# MOTOR.net
KiCad netlist of a schematic drawn in Altium Designer
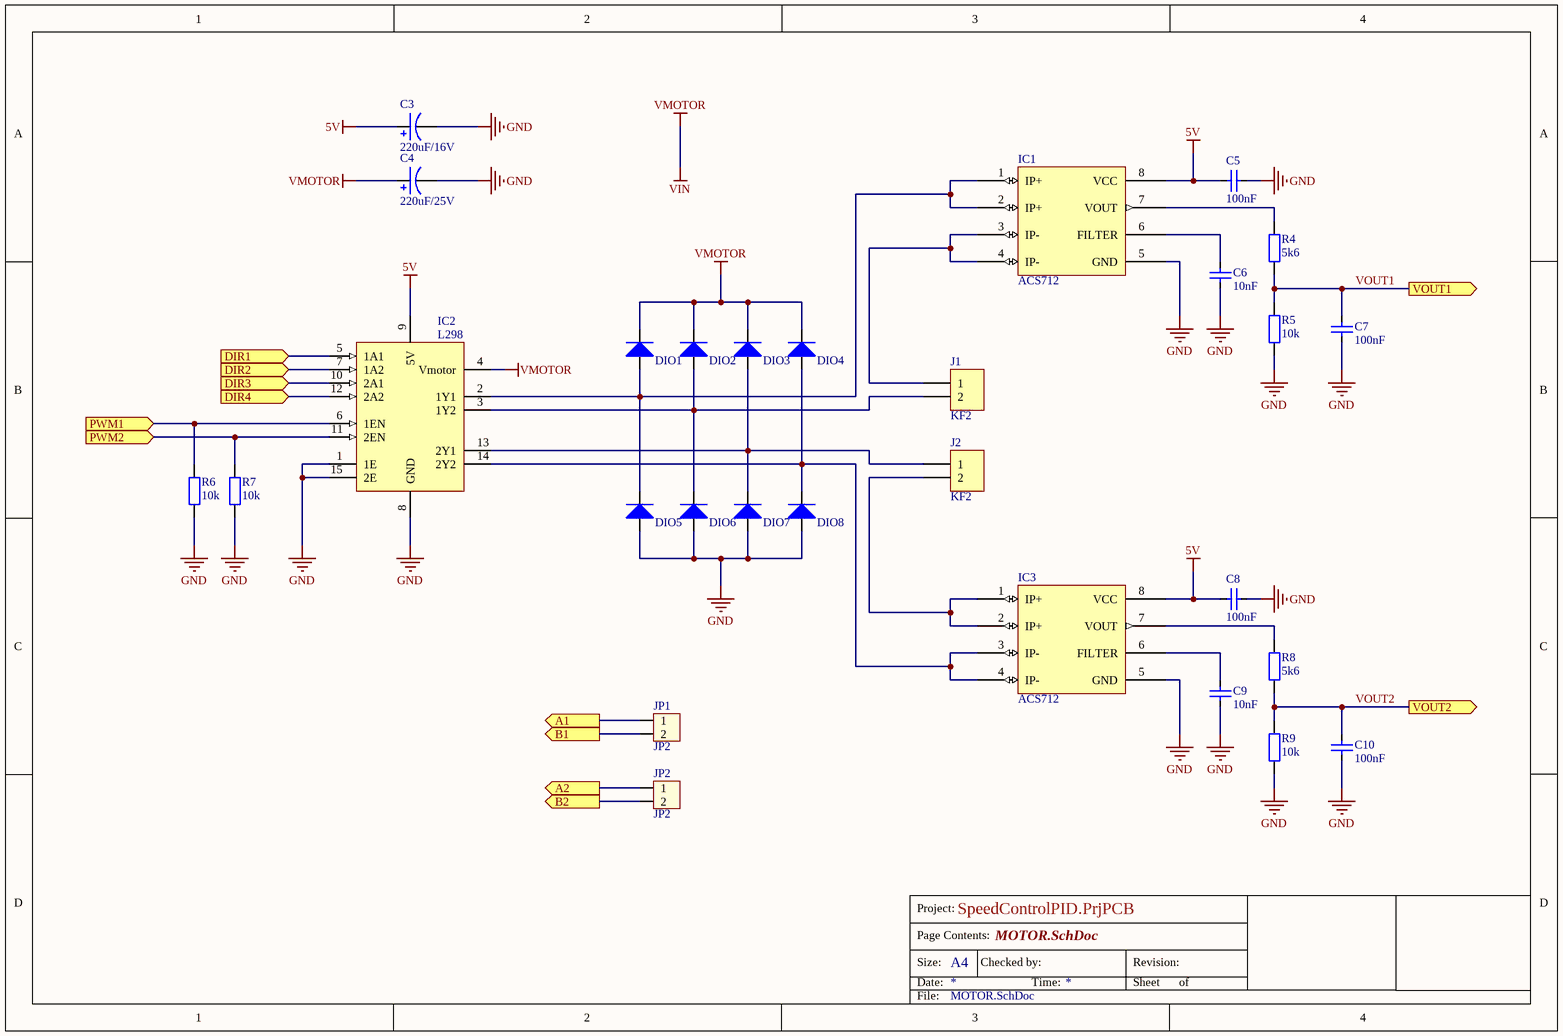
[diagram p0: MOTOR.SchDoc]

(export (version "E")
  (design (tool "Eeschema 10.0.6"))
  (components
    (comp (ref "C3")
      (value "220uF/16V")
      (footprint "C8mm")
      (description "Polarized Capacitor (Axial)")
      (fields (field (name "PUBLISHER") "Altium Limited"))
      (libsource (lib "My Library") (part "Cap Pol"))
    )
    (comp (ref "C4")
      (value "220uF/25V")
      (footprint "C8mm")
      (description "Polarized Capacitor (Axial)")
      (fields (field (name "PUBLISHER") "Altium Limited"))
      (libsource (lib "My Library") (part "Cap Pol"))
    )
    (comp (ref "C5")
      (value "100nF")
      (footprint "CAP_0805")
      (description "Capacitor")
      (fields (field (name "PUBLISHER") "Altium Limited"))
      (libsource (lib "My Library") (part "CapSMD"))
    )
    (comp (ref "C6")
      (value "10nF")
      (footprint "CAP_0805")
      (description "Capacitor")
      (fields (field (name "PUBLISHER") "Altium Limited"))
      (libsource (lib "My Library") (part "CapSMD"))
    )
    (comp (ref "C7")
      (value "100nF")
      (footprint "CAP_0805")
      (description "Capacitor")
      (fields (field (name "PUBLISHER") "Altium Limited"))
      (libsource (lib "My Library") (part "CapSMD"))
    )
    (comp (ref "C8")
      (value "100nF")
      (footprint "CAP_0805")
      (description "Capacitor")
      (fields (field (name "PUBLISHER") "Altium Limited"))
      (libsource (lib "My Library") (part "CapSMD"))
    )
    (comp (ref "C9")
      (value "10nF")
      (footprint "CAP_0805")
      (description "Capacitor")
      (fields (field (name "PUBLISHER") "Altium Limited"))
      (libsource (lib "My Library") (part "CapSMD"))
    )
    (comp (ref "C10")
      (value "100nF")
      (footprint "CAP_0805")
      (description "Capacitor")
      (fields (field (name "PUBLISHER") "Altium Limited"))
      (libsource (lib "My Library") (part "CapSMD"))
    )
    (comp (ref "DIO1")
      (value "Diode SMD")
      (footprint "DIO-214AC(SMA)")
      (description "Default Diode")
      (fields (field (name "PUBLISHER") "Altium Limited"))
      (libsource (lib "My Library") (part "Diode SMD"))
    )
    (comp (ref "DIO2")
      (value "Diode SMD")
      (footprint "DIO-214AC(SMA)")
      (description "Default Diode")
      (fields (field (name "PUBLISHER") "Altium Limited"))
      (libsource (lib "My Library") (part "Diode SMD"))
    )
    (comp (ref "DIO3")
      (value "Diode SMD")
      (footprint "DIO-214AC(SMA)")
      (description "Default Diode")
      (fields (field (name "PUBLISHER") "Altium Limited"))
      (libsource (lib "My Library") (part "Diode SMD"))
    )
    (comp (ref "DIO4")
      (value "Diode SMD")
      (footprint "DIO-214AC(SMA)")
      (description "Default Diode")
      (fields (field (name "PUBLISHER") "Altium Limited"))
      (libsource (lib "My Library") (part "Diode SMD"))
    )
    (comp (ref "DIO5")
      (value "Diode SMD")
      (footprint "DIO-214AC(SMA)")
      (description "Default Diode")
      (fields (field (name "PUBLISHER") "Altium Limited"))
      (libsource (lib "My Library") (part "Diode SMD"))
    )
    (comp (ref "DIO6")
      (value "Diode SMD")
      (footprint "DIO-214AC(SMA)")
      (description "Default Diode")
      (fields (field (name "PUBLISHER") "Altium Limited"))
      (libsource (lib "My Library") (part "Diode SMD"))
    )
    (comp (ref "DIO7")
      (value "Diode SMD")
      (footprint "DIO-214AC(SMA)")
      (description "Default Diode")
      (fields (field (name "PUBLISHER") "Altium Limited"))
      (libsource (lib "My Library") (part "Diode SMD"))
    )
    (comp (ref "DIO8")
      (value "Diode SMD")
      (footprint "DIO-214AC(SMA)")
      (description "Default Diode")
      (fields (field (name "PUBLISHER") "Altium Limited"))
      (libsource (lib "My Library") (part "Diode SMD"))
    )
    (comp (ref "IC1") (value "ACS712") (footprint "SOIC-8") (libsource (lib "My Library") (part "ACS712")))
    (comp (ref "IC2")
      (value "L298")
      (footprint "DIP15SL2")
      (description "Dual Full-H Driver")
      (fields (field (name "PUBLISHER") "Altium Limited"))
      (libsource (lib "My Library") (part "L298"))
    )
    (comp (ref "IC3") (value "ACS712") (footprint "SOIC-8") (libsource (lib "My Library") (part "ACS712")))
    (comp (ref "J1")
      (value "KF2")
      (footprint "KF2-5.08")
      (fields
        (field (name "MANUFACTURER") "Würth Elektronik eiSos GmbH")
        (field (name "PARTNO") "691103110002")
        (field (name "CREATED BY") "Karrer Zheng")
      )
      (libsource (lib "My Library") (part "KF2"))
    )
    (comp (ref "J2")
      (value "KF2")
      (footprint "KF2-5.08")
      (fields
        (field (name "MANUFACTURER") "Würth Elektronik eiSos GmbH")
        (field (name "PARTNO") "691103110002")
        (field (name "CREATED BY") "Karrer Zheng")
      )
      (libsource (lib "My Library") (part "KF2"))
    )
    (comp (ref "JP1")
      (value "JP2")
      (footprint "CON2")
      (description "Connector 2")
      (libsource (lib "My Library") (part "Con2"))
    )
    (comp (ref "JP2")
      (value "JP2")
      (footprint "CON2")
      (description "Connector 2")
      (libsource (lib "My Library") (part "Con2"))
    )
    (comp (ref "R4")
      (value "5k6")
      (footprint "RES-SMD-0805")
      (description "Resistor SMD")
      (fields
        (field (name "MANUFACTURER") "Generic Components")
        (field (name "PUBLISHER") "Altium Hobart Technology Centre")
      )
      (libsource (lib "My Library") (part "Resistor - SMD"))
    )
    (comp (ref "R5")
      (value "10k")
      (footprint "RES-SMD-0805")
      (description "Resistor SMD")
      (fields
        (field (name "MANUFACTURER") "Generic Components")
        (field (name "PUBLISHER") "Altium Hobart Technology Centre")
      )
      (libsource (lib "My Library") (part "Resistor - SMD"))
    )
    (comp (ref "R6")
      (value "10k")
      (footprint "RES-SMD-0805")
      (description "Resistor SMD")
      (fields
        (field (name "MANUFACTURER") "Generic Components")
        (field (name "PUBLISHER") "Altium Hobart Technology Centre")
      )
      (libsource (lib "My Library") (part "Resistor - SMD"))
    )
    (comp (ref "R7")
      (value "10k")
      (footprint "RES-SMD-0805")
      (description "Resistor SMD")
      (fields
        (field (name "MANUFACTURER") "Generic Components")
        (field (name "PUBLISHER") "Altium Hobart Technology Centre")
      )
      (libsource (lib "My Library") (part "Resistor - SMD"))
    )
    (comp (ref "R8")
      (value "5k6")
      (footprint "RES-SMD-0805")
      (description "Resistor SMD")
      (fields
        (field (name "MANUFACTURER") "Generic Components")
        (field (name "PUBLISHER") "Altium Hobart Technology Centre")
      )
      (libsource (lib "My Library") (part "Resistor - SMD"))
    )
    (comp (ref "R9")
      (value "10k")
      (footprint "RES-SMD-0805")
      (description "Resistor SMD")
      (fields
        (field (name "MANUFACTURER") "Generic Components")
        (field (name "PUBLISHER") "Altium Hobart Technology Centre")
      )
      (libsource (lib "My Library") (part "Resistor - SMD"))
    )
  )
  (nets
    (net (code "1") (name "/A1") (class "Default")
      (node (ref "JP1") (pin "1") (pinfunction "1_1") (pintype "passive"))
    )
    (net (code "2") (name "/A2") (class "Default")
      (node (ref "JP2") (pin "1") (pinfunction "1_1") (pintype "passive"))
    )
    (net (code "3") (name "/B1") (class "Default")
      (node (ref "JP1") (pin "2") (pinfunction "2_2") (pintype "passive"))
    )
    (net (code "4") (name "/B2") (class "Default")
      (node (ref "JP2") (pin "2") (pinfunction "2_2") (pintype "passive"))
    )
    (net (code "5") (name "/DIR1") (class "Default")
      (node (ref "IC2") (pin "5") (pinfunction "1A1_5") (pintype "input"))
    )
    (net (code "6") (name "/DIR2") (class "Default")
      (node (ref "IC2") (pin "7") (pinfunction "1A2_7") (pintype "input"))
    )
    (net (code "7") (name "/DIR3") (class "Default")
      (node (ref "IC2") (pin "10") (pinfunction "2A1_10") (pintype "input"))
    )
    (net (code "8") (name "/DIR4") (class "Default")
      (node (ref "IC2") (pin "12") (pinfunction "2A2_12") (pintype "input"))
    )
    (net (code "9") (name "/PWM1") (class "Default")
      (node (ref "IC2") (pin "6") (pinfunction "1EN_6") (pintype "input"))
      (node (ref "R6") (pin "1") (pinfunction "1_1") (pintype "passive"))
    )
    (net (code "10") (name "/PWM2") (class "Default")
      (node (ref "IC2") (pin "11") (pinfunction "2EN_11") (pintype "input"))
      (node (ref "R7") (pin "1") (pinfunction "1_1") (pintype "passive"))
    )
    (net (code "11") (name "/VOUT1") (class "Default")
      (node (ref "C7") (pin "2") (pinfunction "2_2") (pintype "passive"))
      (node (ref "R4") (pin "2") (pinfunction "2_2") (pintype "passive"))
      (node (ref "R5") (pin "1") (pinfunction "1_1") (pintype "passive"))
    )
    (net (code "12") (name "/VOUT2") (class "Default")
      (node (ref "C10") (pin "2") (pinfunction "2_2") (pintype "passive"))
      (node (ref "R8") (pin "2") (pinfunction "2_2") (pintype "passive"))
      (node (ref "R9") (pin "1") (pinfunction "1_1") (pintype "passive"))
    )
    (net (code "13") (name "5V") (class "Default")
      (node (ref "C3") (pin "1") (pinfunction "1_1") (pintype "passive"))
      (node (ref "C5") (pin "2") (pinfunction "2_2") (pintype "passive"))
      (node (ref "C8") (pin "2") (pinfunction "2_2") (pintype "passive"))
      (node (ref "IC1") (pin "8") (pinfunction "VCC_8") (pintype "passive"))
      (node (ref "IC2") (pin "9") (pinfunction "5V_9") (pintype "power_in"))
      (node (ref "IC3") (pin "8") (pinfunction "VCC_8") (pintype "passive"))
    )
    (net (code "14") (name "GND") (class "Default")
      (node (ref "C10") (pin "1") (pinfunction "1_1") (pintype "passive"))
      (node (ref "C3") (pin "2") (pinfunction "2_2") (pintype "passive"))
      (node (ref "C4") (pin "2") (pinfunction "2_2") (pintype "passive"))
      (node (ref "C5") (pin "1") (pinfunction "1_1") (pintype "passive"))
      (node (ref "C6") (pin "1") (pinfunction "1_1") (pintype "passive"))
      (node (ref "C7") (pin "1") (pinfunction "1_1") (pintype "passive"))
      (node (ref "C8") (pin "1") (pinfunction "1_1") (pintype "passive"))
      (node (ref "C9") (pin "1") (pinfunction "1_1") (pintype "passive"))
      (node (ref "DIO5") (pin "1") (pinfunction "A_1") (pintype "passive"))
      (node (ref "DIO6") (pin "1") (pinfunction "A_1") (pintype "passive"))
      (node (ref "DIO7") (pin "1") (pinfunction "A_1") (pintype "passive"))
      (node (ref "DIO8") (pin "1") (pinfunction "A_1") (pintype "passive"))
      (node (ref "IC1") (pin "5") (pinfunction "GND_5") (pintype "passive"))
      (node (ref "IC2") (pin "1") (pinfunction "1E_1") (pintype "passive"))
      (node (ref "IC2") (pin "15") (pinfunction "2E_15") (pintype "passive"))
      (node (ref "IC2") (pin "8") (pinfunction "GND_8") (pintype "power_in"))
      (node (ref "IC3") (pin "5") (pinfunction "GND_5") (pintype "passive"))
      (node (ref "R5") (pin "2") (pinfunction "2_2") (pintype "passive"))
      (node (ref "R6") (pin "2") (pinfunction "2_2") (pintype "passive"))
      (node (ref "R7") (pin "2") (pinfunction "2_2") (pintype "passive"))
      (node (ref "R9") (pin "2") (pinfunction "2_2") (pintype "passive"))
    )
    (net (code "15") (name "Net-(DIO1-A)") (class "Default")
      (node (ref "DIO1") (pin "1") (pinfunction "A_1") (pintype "passive"))
      (node (ref "DIO5") (pin "2") (pinfunction "K_2") (pintype "passive"))
      (node (ref "IC1") (pin "1") (pinfunction "IP+_1") (pintype "bidirectional"))
      (node (ref "IC1") (pin "2") (pinfunction "IP+_2") (pintype "bidirectional"))
      (node (ref "IC2") (pin "2") (pinfunction "1Y1_2") (pintype "tri_state"))
    )
    (net (code "16") (name "Net-(DIO2-A)") (class "Default")
      (node (ref "DIO2") (pin "1") (pinfunction "A_1") (pintype "passive"))
      (node (ref "DIO6") (pin "2") (pinfunction "K_2") (pintype "passive"))
      (node (ref "IC2") (pin "3") (pinfunction "1Y2_3") (pintype "tri_state"))
      (node (ref "J1") (pin "2") (pinfunction "2_2") (pintype "passive"))
    )
    (net (code "17") (name "Net-(DIO3-A)") (class "Default")
      (node (ref "DIO3") (pin "1") (pinfunction "A_1") (pintype "passive"))
      (node (ref "DIO7") (pin "2") (pinfunction "K_2") (pintype "passive"))
      (node (ref "IC2") (pin "13") (pinfunction "2Y1_13") (pintype "tri_state"))
      (node (ref "J2") (pin "1") (pinfunction "1_1") (pintype "passive"))
    )
    (net (code "18") (name "Net-(DIO4-A)") (class "Default")
      (node (ref "DIO4") (pin "1") (pinfunction "A_1") (pintype "passive"))
      (node (ref "DIO8") (pin "2") (pinfunction "K_2") (pintype "passive"))
      (node (ref "IC2") (pin "14") (pinfunction "2Y2_14") (pintype "tri_state"))
      (node (ref "IC3") (pin "3") (pinfunction "IP-_3") (pintype "bidirectional"))
      (node (ref "IC3") (pin "4") (pinfunction "IP-_4") (pintype "bidirectional"))
    )
    (net (code "19") (name "Net-(IC1-FILTER)") (class "Default")
      (node (ref "C6") (pin "2") (pinfunction "2_2") (pintype "passive"))
      (node (ref "IC1") (pin "6") (pinfunction "FILTER_6") (pintype "passive"))
    )
    (net (code "20") (name "Net-(IC1-IP--Pad3)") (class "Default")
      (node (ref "IC1") (pin "3") (pinfunction "IP-_3") (pintype "bidirectional"))
      (node (ref "IC1") (pin "4") (pinfunction "IP-_4") (pintype "bidirectional"))
      (node (ref "J1") (pin "1") (pinfunction "1_1") (pintype "passive"))
    )
    (net (code "21") (name "Net-(IC1-VOUT)") (class "Default")
      (node (ref "IC1") (pin "7") (pinfunction "VOUT_7") (pintype "output"))
      (node (ref "R4") (pin "1") (pinfunction "1_1") (pintype "passive"))
    )
    (net (code "22") (name "Net-(IC3-FILTER)") (class "Default")
      (node (ref "C9") (pin "2") (pinfunction "2_2") (pintype "passive"))
      (node (ref "IC3") (pin "6") (pinfunction "FILTER_6") (pintype "passive"))
    )
    (net (code "23") (name "Net-(IC3-IP+-Pad1)") (class "Default")
      (node (ref "IC3") (pin "1") (pinfunction "IP+_1") (pintype "bidirectional"))
      (node (ref "IC3") (pin "2") (pinfunction "IP+_2") (pintype "bidirectional"))
      (node (ref "J2") (pin "2") (pinfunction "2_2") (pintype "passive"))
    )
    (net (code "24") (name "Net-(IC3-VOUT)") (class "Default")
      (node (ref "IC3") (pin "7") (pinfunction "VOUT_7") (pintype "output"))
      (node (ref "R8") (pin "1") (pinfunction "1_1") (pintype "passive"))
    )
    (net (code "25") (name "VIN") (class "Default")
      (node (ref "C4") (pin "1") (pinfunction "1_1") (pintype "passive"))
      (node (ref "DIO1") (pin "2") (pinfunction "K_2") (pintype "passive"))
      (node (ref "DIO2") (pin "2") (pinfunction "K_2") (pintype "passive"))
      (node (ref "DIO3") (pin "2") (pinfunction "K_2") (pintype "passive"))
      (node (ref "DIO4") (pin "2") (pinfunction "K_2") (pintype "passive"))
      (node (ref "IC2") (pin "4") (pinfunction "Vmotor_4") (pintype "power_in"))
    )
  )
)
